# Addon-mapleCUx_Raspi-3V3-UART-CC2530-V02.net
KiCad netlist of a schematic drawn in EAGLE
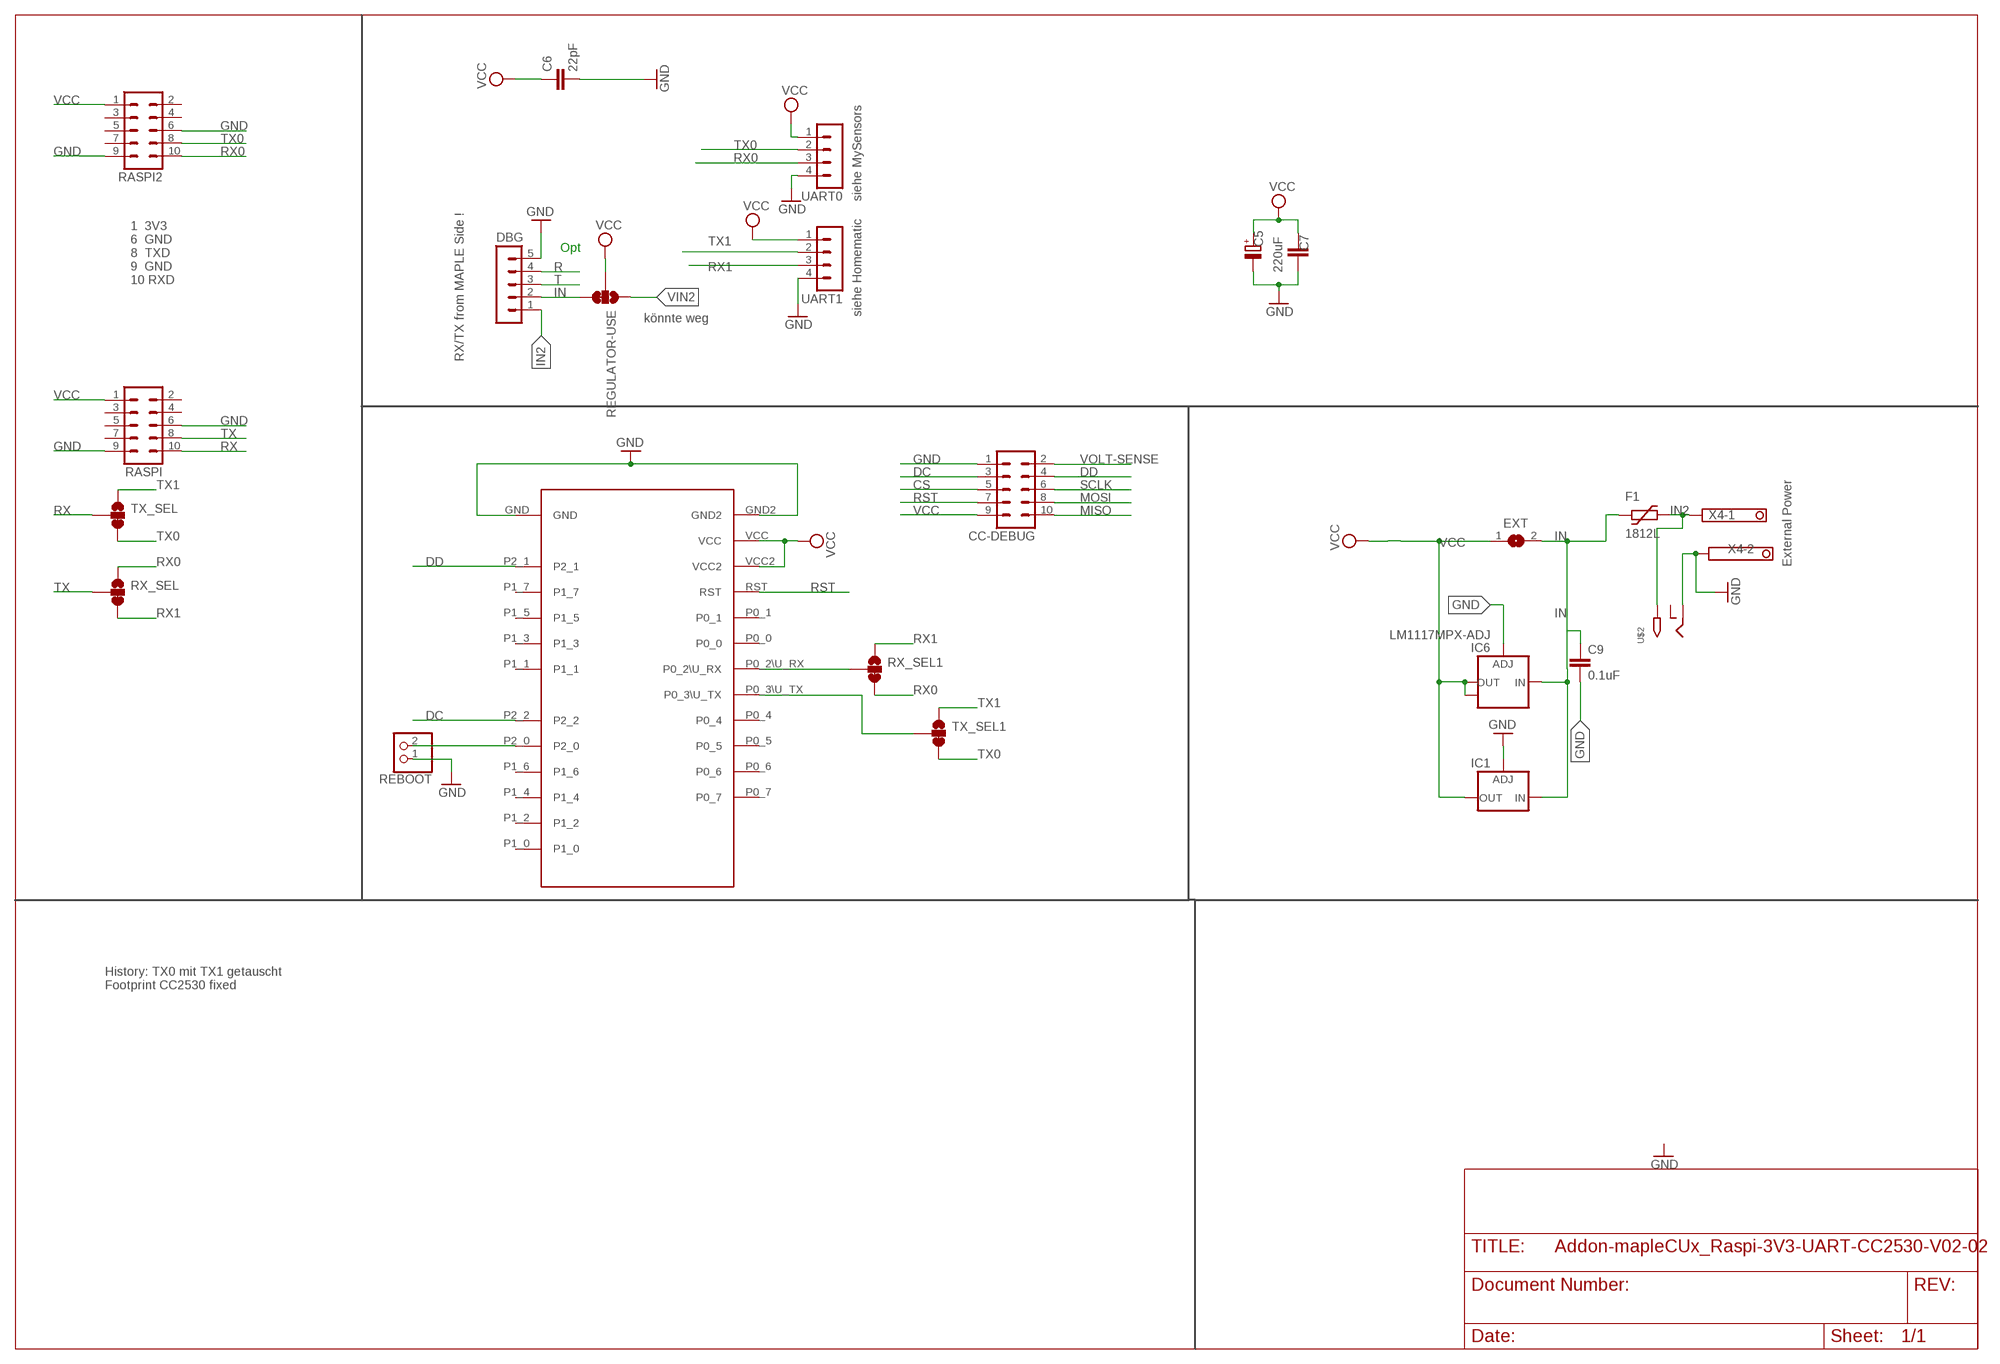
[diagram p0: schematic, sheet 1]

(export (version "E")
  (design (tool "Eeschema 10.0.6"))
  (components
    (comp (ref "C5")
      (value "220uF")
      (footprint "eagle-import:E5-8,5")
      (libsource (lib "eagle-import") (part "CPOL-EUE5-8.5"))
    )
    (comp (ref "C6")
      (value "22pF")
      (footprint "eagle-import:C0805")
      (libsource (lib "eagle-import") (part "C-EUC0805"))
    )
    (comp (ref "C7")
      (value "C-EUC1812")
      (footprint "eagle-import:C1812")
      (libsource (lib "eagle-import") (part "C-EUC1812"))
    )
    (comp (ref "C9")
      (value "0.1uF")
      (footprint "eagle-import:C1206")
      (libsource (lib "eagle-import") (part "C-EUC1206"))
    )
    (comp (ref "CC-DEBUG")
      (value "MA05-2")
      (footprint "eagle-import:MA05-2")
      (libsource (lib "eagle-import") (part "MA05-2"))
    )
    (comp (ref "DBG")
      (value "MA05-1")
      (footprint "eagle-import:MA05-1")
      (libsource (lib "eagle-import") (part "MA05-1"))
    )
    (comp (ref "EXT") (value "SJ") (footprint "eagle-import:SJ") (libsource (lib "eagle-import") (part "SJ")))
    (comp (ref "F1")
      (value "1812L")
      (footprint "eagle-import:1812L")
      (libsource (lib "eagle-import") (part "1812L"))
    )
    (comp (ref "IC1")
      (value "LD117ADT50TR")
      (footprint "eagle-import:DPACK")
      (libsource (lib "eagle-import") (part "LD117A?DT50TR"))
    )
    (comp (ref "IC6")
      (value "LM1117MPX-ADJ")
      (footprint "eagle-import:SOT223")
      (libsource (lib "eagle-import") (part "LM1117MPX-ADJ"))
    )
    (comp (ref "RASPI")
      (value "MA05-2")
      (footprint "eagle-import:MA05-2")
      (libsource (lib "eagle-import") (part "MA05-2"))
    )
    (comp (ref "RASPI2")
      (value "MA05-2")
      (footprint "eagle-import:MA05-2")
      (libsource (lib "eagle-import") (part "MA05-2"))
    )
    (comp (ref "REBOOT")
      (value "PINHD-1X2")
      (footprint "eagle-import:1X02")
      (libsource (lib "eagle-import") (part "PINHD-1X2"))
    )
    (comp (ref "REGULATOR-USE")
      (value "JUMPER-SMT_3_1-NC_TRACE_SILK")
      (footprint "eagle-import:SMT-JUMPER_3_1-NC_TRACE_SILK")
      (libsource (lib "eagle-import") (part "JUMPER-SMT_3_1-NC_TRACE_SILK"))
    )
    (comp (ref "RX_SEL")
      (value "JUMPER-SMT_3_1-NC_TRACE_SILK")
      (footprint "eagle-import:SMT-JUMPER_3_1-NC_TRACE_SILK")
      (libsource (lib "eagle-import") (part "JUMPER-SMT_3_1-NC_TRACE_SILK"))
    )
    (comp (ref "RX_SEL1")
      (value "JUMPER-SMT_3_1-NC_TRACE_SILK")
      (footprint "eagle-import:SMT-JUMPER_3_1-NC_TRACE_SILK")
      (libsource (lib "eagle-import") (part "JUMPER-SMT_3_1-NC_TRACE_SILK"))
    )
    (comp (ref "TX_SEL")
      (value "JUMPER-SMT_3_1-NC_TRACE_SILK")
      (footprint "eagle-import:SMT-JUMPER_3_1-NC_TRACE_SILK")
      (libsource (lib "eagle-import") (part "JUMPER-SMT_3_1-NC_TRACE_SILK"))
    )
    (comp (ref "TX_SEL1")
      (value "JUMPER-SMT_3_1-NC_TRACE_SILK")
      (footprint "eagle-import:SMT-JUMPER_3_1-NC_TRACE_SILK")
      (libsource (lib "eagle-import") (part "JUMPER-SMT_3_1-NC_TRACE_SILK"))
    )
    (comp (ref "U$2")
      (value "2.1MMJACKTHM")
      (footprint "eagle-import:PJ-102A")
      (libsource (lib "eagle-import") (part "2.1MMJACKTHM"))
    )
    (comp (ref "U$3")
      (value "CC2530_MODULE")
      (footprint "eagle-import:CC2530_DIL")
      (libsource (lib "eagle-import") (part "CC2530_MODULE"))
    )
    (comp (ref "UART0")
      (value "MA04-1")
      (footprint "eagle-import:MA04-1")
      (libsource (lib "eagle-import") (part "MA04-1"))
    )
    (comp (ref "UART1")
      (value "MA04-1")
      (footprint "eagle-import:MA04-1")
      (libsource (lib "eagle-import") (part "MA04-1"))
    )
    (comp (ref "X4")
      (value "1751248")
      (footprint "eagle-import:1751248")
      (libsource (lib "eagle-import") (part "1751248"))
    )
  )
  (nets
    (net (code "1") (name "/CS") (class "Default")
      (node (ref "CC-DEBUG") (pin "5") (pinfunction "5_5") (pintype "passive"))
    )
    (net (code "2") (name "/DC") (class "Default")
      (node (ref "CC-DEBUG") (pin "3") (pinfunction "3_3") (pintype "passive"))
      (node (ref "U$3") (pin "P2_2") (pinfunction "P2_2_P2_2") (pintype "bidirectional"))
    )
    (net (code "3") (name "/DD") (class "Default")
      (node (ref "CC-DEBUG") (pin "4") (pinfunction "4_4") (pintype "passive"))
      (node (ref "U$3") (pin "P2_1") (pinfunction "P2_1_P2_1") (pintype "bidirectional"))
    )
    (net (code "4") (name "/IN") (class "Default")
      (node (ref "C9") (pin "1") (pinfunction "1_1") (pintype "passive"))
      (node (ref "DBG") (pin "2") (pinfunction "2_2") (pintype "passive"))
      (node (ref "EXT") (pin "2") (pinfunction "2_2") (pintype "passive"))
      (node (ref "F1") (pin "P$1") (pinfunction "1_P$1") (pintype "passive"))
      (node (ref "IC1") (pin "3") (pinfunction "IN_3") (pintype "input"))
      (node (ref "IC6") (pin "3") (pinfunction "IN_3") (pintype "input"))
      (node (ref "REGULATOR-USE") (pin "3") (pinfunction "3_3") (pintype "passive"))
    )
    (net (code "5") (name "/MISO") (class "Default")
      (node (ref "CC-DEBUG") (pin "10") (pinfunction "10_10") (pintype "passive"))
    )
    (net (code "6") (name "/MOSI") (class "Default")
      (node (ref "CC-DEBUG") (pin "8") (pinfunction "8_8") (pintype "passive"))
    )
    (net (code "7") (name "/R") (class "Default")
      (node (ref "DBG") (pin "4") (pinfunction "4_4") (pintype "passive"))
    )
    (net (code "8") (name "/RST") (class "Default")
      (node (ref "CC-DEBUG") (pin "7") (pinfunction "7_7") (pintype "passive"))
      (node (ref "U$3") (pin "RST") (pinfunction "RST_RST") (pintype "bidirectional"))
    )
    (net (code "9") (name "/RX") (class "Default")
      (node (ref "RASPI") (pin "10") (pinfunction "10_10") (pintype "passive"))
      (node (ref "TX_SEL") (pin "2") (pinfunction "2_2") (pintype "passive"))
    )
    (net (code "10") (name "/RX0") (class "Default")
      (node (ref "RASPI2") (pin "10") (pinfunction "10_10") (pintype "passive"))
      (node (ref "RX_SEL") (pin "1") (pinfunction "1_1") (pintype "passive"))
      (node (ref "RX_SEL1") (pin "3") (pinfunction "3_3") (pintype "passive"))
      (node (ref "UART0") (pin "3") (pinfunction "3_3") (pintype "passive"))
    )
    (net (code "11") (name "/RX1") (class "Default")
      (node (ref "RX_SEL") (pin "3") (pinfunction "3_3") (pintype "passive"))
      (node (ref "RX_SEL1") (pin "1") (pinfunction "1_1") (pintype "passive"))
      (node (ref "UART1") (pin "3") (pinfunction "3_3") (pintype "passive"))
    )
    (net (code "12") (name "/SCLK") (class "Default")
      (node (ref "CC-DEBUG") (pin "6") (pinfunction "6_6") (pintype "passive"))
    )
    (net (code "13") (name "/T") (class "Default")
      (node (ref "DBG") (pin "3") (pinfunction "3_3") (pintype "passive"))
    )
    (net (code "14") (name "/TX") (class "Default")
      (node (ref "RASPI") (pin "8") (pinfunction "8_8") (pintype "passive"))
      (node (ref "RX_SEL") (pin "2") (pinfunction "2_2") (pintype "passive"))
    )
    (net (code "15") (name "/TX0") (class "Default")
      (node (ref "RASPI2") (pin "8") (pinfunction "8_8") (pintype "passive"))
      (node (ref "TX_SEL") (pin "3") (pinfunction "3_3") (pintype "passive"))
      (node (ref "TX_SEL1") (pin "3") (pinfunction "3_3") (pintype "passive"))
      (node (ref "UART0") (pin "2") (pinfunction "2_2") (pintype "passive"))
    )
    (net (code "16") (name "/TX1") (class "Default")
      (node (ref "TX_SEL") (pin "1") (pinfunction "1_1") (pintype "passive"))
      (node (ref "TX_SEL1") (pin "1") (pinfunction "1_1") (pintype "passive"))
      (node (ref "UART1") (pin "2") (pinfunction "2_2") (pintype "passive"))
    )
    (net (code "17") (name "/VOLT-SENSE") (class "Default")
      (node (ref "CC-DEBUG") (pin "2") (pinfunction "2_2") (pintype "passive"))
    )
    (net (code "18") (name "GND") (class "Default")
      (node (ref "C5") (pin "-") (pinfunction "-_-") (pintype "passive"))
      (node (ref "C6") (pin "2") (pinfunction "2_2") (pintype "passive"))
      (node (ref "C7") (pin "1") (pinfunction "1_1") (pintype "passive"))
      (node (ref "C9") (pin "2") (pinfunction "2_2") (pintype "passive"))
      (node (ref "CC-DEBUG") (pin "1") (pinfunction "1_1") (pintype "passive"))
      (node (ref "DBG") (pin "5") (pinfunction "5_5") (pintype "passive"))
      (node (ref "IC1") (pin "1") (pinfunction "ADJ_1") (pintype "input"))
      (node (ref "IC6") (pin "1") (pinfunction "ADJ_1") (pintype "input"))
      (node (ref "RASPI") (pin "6") (pinfunction "6_6") (pintype "passive"))
      (node (ref "RASPI") (pin "9") (pinfunction "9_9") (pintype "passive"))
      (node (ref "RASPI2") (pin "6") (pinfunction "6_6") (pintype "passive"))
      (node (ref "RASPI2") (pin "9") (pinfunction "9_9") (pintype "passive"))
      (node (ref "REBOOT") (pin "1") (pinfunction "1_1") (pintype "passive"))
      (node (ref "U$2") (pin "RING") (pinfunction "RING_RING") (pintype "bidirectional"))
      (node (ref "U$3") (pin "GND") (pinfunction "GND_GND") (pintype "bidirectional"))
      (node (ref "U$3") (pin "GND2") (pinfunction "GND2_GND2") (pintype "bidirectional"))
      (node (ref "UART0") (pin "4") (pinfunction "4_4") (pintype "passive"))
      (node (ref "UART1") (pin "4") (pinfunction "4_4") (pintype "passive"))
      (node (ref "X4") (pin "2") (pinfunction "K_2") (pintype "passive"))
    )
    (net (code "19") (name "IN2") (class "Default")
      (node (ref "DBG") (pin "1") (pinfunction "1_1") (pintype "passive"))
      (node (ref "F1") (pin "P$2") (pinfunction "2_P$2") (pintype "passive"))
      (node (ref "U$2") (pin "TIP") (pinfunction "TIP_TIP") (pintype "bidirectional"))
      (node (ref "X4") (pin "1") (pinfunction "K_1") (pintype "passive"))
    )
    (net (code "20") (name "Net-(REBOOT-Pad2)") (class "Default")
      (node (ref "REBOOT") (pin "2") (pinfunction "2_2") (pintype "passive"))
      (node (ref "U$3") (pin "P2_0") (pinfunction "P2_0_P2_0") (pintype "bidirectional"))
    )
    (net (code "21") (name "Net-(RX_SEL1-Pad2)") (class "Default")
      (node (ref "RX_SEL1") (pin "2") (pinfunction "2_2") (pintype "passive"))
      (node (ref "U$3") (pin "P0_2\\U_RX") (pinfunction "P0_2\\U_RX_P0_2\\U_RX") (pintype "bidirectional"))
    )
    (net (code "22") (name "Net-(TX_SEL1-Pad2)") (class "Default")
      (node (ref "TX_SEL1") (pin "2") (pinfunction "2_2") (pintype "passive"))
      (node (ref "U$3") (pin "P0_3\\U_TX") (pinfunction "P0_3\\U_TX_P0_3\\U_TX") (pintype "bidirectional"))
    )
    (net (code "23") (name "VCC") (class "Default")
      (node (ref "C5") (pin "+") (pinfunction "+_+") (pintype "passive"))
      (node (ref "C6") (pin "1") (pinfunction "1_1") (pintype "passive"))
      (node (ref "C7") (pin "2") (pinfunction "2_2") (pintype "passive"))
      (node (ref "CC-DEBUG") (pin "9") (pinfunction "9_9") (pintype "passive"))
      (node (ref "EXT") (pin "1") (pinfunction "1_1") (pintype "passive"))
      (node (ref "IC1") (pin "4") (pinfunction "OUT_4") (pintype "passive"))
      (node (ref "IC6") (pin "2") (pinfunction "OUT_2") (pintype "passive"))
      (node (ref "IC6") (pin "TAB") (pinfunction "OUT1_TAB") (pintype "passive"))
      (node (ref "RASPI") (pin "1") (pinfunction "1_1") (pintype "passive"))
      (node (ref "RASPI2") (pin "1") (pinfunction "1_1") (pintype "passive"))
      (node (ref "REGULATOR-USE") (pin "2") (pinfunction "2_2") (pintype "passive"))
      (node (ref "U$3") (pin "VCC") (pinfunction "VCC_VCC") (pintype "bidirectional"))
      (node (ref "U$3") (pin "VCC2") (pinfunction "VCC2_VCC2") (pintype "bidirectional"))
      (node (ref "UART0") (pin "1") (pinfunction "1_1") (pintype "passive"))
      (node (ref "UART1") (pin "1") (pinfunction "1_1") (pintype "passive"))
    )
    (net (code "24") (name "VIN2") (class "Default")
      (node (ref "REGULATOR-USE") (pin "1") (pinfunction "1_1") (pintype "passive"))
    )
    (net (code "25") (name "unconnected-(RASPI-Pad2)") (class "Default")
      (node (ref "RASPI") (pin "2") (pinfunction "2_2") (pintype "passive"))
    )
    (net (code "26") (name "unconnected-(RASPI-Pad3)") (class "Default")
      (node (ref "RASPI") (pin "3") (pinfunction "3_3") (pintype "passive"))
    )
    (net (code "27") (name "unconnected-(RASPI-Pad4)") (class "Default")
      (node (ref "RASPI") (pin "4") (pinfunction "4_4") (pintype "passive"))
    )
    (net (code "28") (name "unconnected-(RASPI-Pad5)") (class "Default")
      (node (ref "RASPI") (pin "5") (pinfunction "5_5") (pintype "passive"))
    )
    (net (code "29") (name "unconnected-(RASPI-Pad7)") (class "Default")
      (node (ref "RASPI") (pin "7") (pinfunction "7_7") (pintype "passive"))
    )
    (net (code "30") (name "unconnected-(RASPI2-Pad2)") (class "Default")
      (node (ref "RASPI2") (pin "2") (pinfunction "2_2") (pintype "passive"))
    )
    (net (code "31") (name "unconnected-(RASPI2-Pad3)") (class "Default")
      (node (ref "RASPI2") (pin "3") (pinfunction "3_3") (pintype "passive"))
    )
    (net (code "32") (name "unconnected-(RASPI2-Pad4)") (class "Default")
      (node (ref "RASPI2") (pin "4") (pinfunction "4_4") (pintype "passive"))
    )
    (net (code "33") (name "unconnected-(RASPI2-Pad5)") (class "Default")
      (node (ref "RASPI2") (pin "5") (pinfunction "5_5") (pintype "passive"))
    )
    (net (code "34") (name "unconnected-(RASPI2-Pad7)") (class "Default")
      (node (ref "RASPI2") (pin "7") (pinfunction "7_7") (pintype "passive"))
    )
    (net (code "35") (name "unconnected-(U$2-PadRING_SW)") (class "Default")
      (node (ref "U$2") (pin "RING_SW") (pinfunction "RING_SW_RING_SW") (pintype "bidirectional"))
    )
    (net (code "36") (name "unconnected-(U$3-PadP0_0)") (class "Default")
      (node (ref "U$3") (pin "P0_0") (pinfunction "P0_0_P0_0") (pintype "bidirectional"))
    )
    (net (code "37") (name "unconnected-(U$3-PadP0_1)") (class "Default")
      (node (ref "U$3") (pin "P0_1") (pinfunction "P0_1_P0_1") (pintype "bidirectional"))
    )
    (net (code "38") (name "unconnected-(U$3-PadP0_4)") (class "Default")
      (node (ref "U$3") (pin "P0_4") (pinfunction "P0_4_P0_4") (pintype "bidirectional"))
    )
    (net (code "39") (name "unconnected-(U$3-PadP0_5)") (class "Default")
      (node (ref "U$3") (pin "P0_5") (pinfunction "P0_5_P0_5") (pintype "bidirectional"))
    )
    (net (code "40") (name "unconnected-(U$3-PadP0_6)") (class "Default")
      (node (ref "U$3") (pin "P0_6") (pinfunction "P0_6_P0_6") (pintype "bidirectional"))
    )
    (net (code "41") (name "unconnected-(U$3-PadP0_7)") (class "Default")
      (node (ref "U$3") (pin "P0_7") (pinfunction "P0_7_P0_7") (pintype "bidirectional"))
    )
    (net (code "42") (name "unconnected-(U$3-PadP1_0)") (class "Default")
      (node (ref "U$3") (pin "P1_0") (pinfunction "P1_0_P1_0") (pintype "bidirectional"))
    )
    (net (code "43") (name "unconnected-(U$3-PadP1_1)") (class "Default")
      (node (ref "U$3") (pin "P1_1") (pinfunction "P1_1_P1_1") (pintype "bidirectional"))
    )
    (net (code "44") (name "unconnected-(U$3-PadP1_2)") (class "Default")
      (node (ref "U$3") (pin "P1_2") (pinfunction "P1_2_P1_2") (pintype "bidirectional"))
    )
    (net (code "45") (name "unconnected-(U$3-PadP1_3)") (class "Default")
      (node (ref "U$3") (pin "P1_3") (pinfunction "P1_3_P1_3") (pintype "bidirectional"))
    )
    (net (code "46") (name "unconnected-(U$3-PadP1_4)") (class "Default")
      (node (ref "U$3") (pin "P1_4") (pinfunction "P1_4_P1_4") (pintype "bidirectional"))
    )
    (net (code "47") (name "unconnected-(U$3-PadP1_5)") (class "Default")
      (node (ref "U$3") (pin "P1_5") (pinfunction "P1_5_P1_5") (pintype "bidirectional"))
    )
    (net (code "48") (name "unconnected-(U$3-PadP1_6)") (class "Default")
      (node (ref "U$3") (pin "P1_6") (pinfunction "P1_6_P1_6") (pintype "bidirectional"))
    )
    (net (code "49") (name "unconnected-(U$3-PadP1_7)") (class "Default")
      (node (ref "U$3") (pin "P1_7") (pinfunction "P1_7_P1_7") (pintype "bidirectional"))
    )
  )
)
